# MEC8_Expansion.net
KiCad netlist of a schematic drawn in Altium Designer
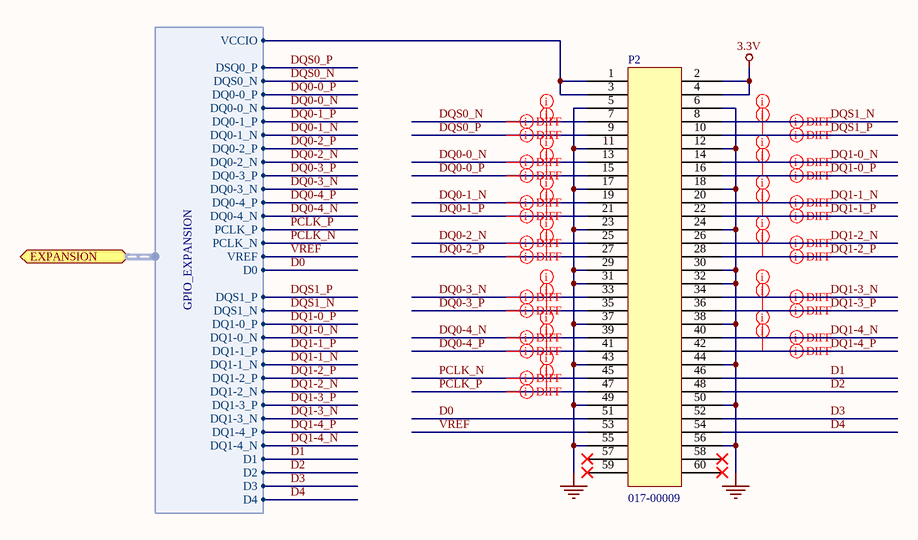
[diagram p0: MEC8_Expansion.SchDoc]

(export (version "E")
  (design (tool "Eeschema 10.0.6"))
  (components
    (comp (ref "P2")
      (value "~")
      (footprint "005-00021")
      (description "CONN RCPT MEC8 60 POS")
      (fields
        (field (name "PART NUMBER") "017-00009")
        (field (name "MANUFACTURER1 PART NUMBER") "MEC8-130-02-L-D-RA1")
      )
      (libsource (lib "CES Component Library") (part "004-00019"))
    )
  )
  (nets
    (net (code "2") (name "/D0") (class "Default")
      (node (ref "P2") (pin "51") (pinfunction "51_51") (pintype "passive"))
    )
    (net (code "3") (name "/D1") (class "Default")
      (node (ref "P2") (pin "46") (pinfunction "46_46") (pintype "passive"))
    )
    (net (code "4") (name "/D2") (class "Default")
      (node (ref "P2") (pin "48") (pinfunction "48_48") (pintype "passive"))
    )
    (net (code "5") (name "/D3") (class "Default")
      (node (ref "P2") (pin "52") (pinfunction "52_52") (pintype "passive"))
    )
    (net (code "6") (name "/D4") (class "Default")
      (node (ref "P2") (pin "54") (pinfunction "54_54") (pintype "passive"))
    )
    (net (code "7") (name "/DQ0-0_N") (class "Default")
      (node (ref "P2") (pin "13") (pinfunction "13_13") (pintype "passive"))
    )
    (net (code "8") (name "/DQ0-0_P") (class "Default")
      (node (ref "P2") (pin "15") (pinfunction "15_15") (pintype "passive"))
    )
    (net (code "9") (name "/DQ0-1_N") (class "Default")
      (node (ref "P2") (pin "19") (pinfunction "19_19") (pintype "passive"))
    )
    (net (code "10") (name "/DQ0-1_P") (class "Default")
      (node (ref "P2") (pin "21") (pinfunction "21_21") (pintype "passive"))
    )
    (net (code "11") (name "/DQ0-2_N") (class "Default")
      (node (ref "P2") (pin "25") (pinfunction "25_25") (pintype "passive"))
    )
    (net (code "12") (name "/DQ0-2_P") (class "Default")
      (node (ref "P2") (pin "27") (pinfunction "27_27") (pintype "passive"))
    )
    (net (code "13") (name "/DQ0-3_N") (class "Default")
      (node (ref "P2") (pin "33") (pinfunction "33_33") (pintype "passive"))
    )
    (net (code "14") (name "/DQ0-3_P") (class "Default")
      (node (ref "P2") (pin "35") (pinfunction "35_35") (pintype "passive"))
    )
    (net (code "15") (name "/DQ0-4_N") (class "Default")
      (node (ref "P2") (pin "39") (pinfunction "39_39") (pintype "passive"))
    )
    (net (code "16") (name "/DQ0-4_P") (class "Default")
      (node (ref "P2") (pin "41") (pinfunction "41_41") (pintype "passive"))
    )
    (net (code "17") (name "/DQ1-0_N") (class "Default")
      (node (ref "P2") (pin "14") (pinfunction "14_14") (pintype "passive"))
    )
    (net (code "18") (name "/DQ1-0_P") (class "Default")
      (node (ref "P2") (pin "16") (pinfunction "16_16") (pintype "passive"))
    )
    (net (code "19") (name "/DQ1-1_N") (class "Default")
      (node (ref "P2") (pin "20") (pinfunction "20_20") (pintype "passive"))
    )
    (net (code "20") (name "/DQ1-1_P") (class "Default")
      (node (ref "P2") (pin "22") (pinfunction "22_22") (pintype "passive"))
    )
    (net (code "21") (name "/DQ1-2_N") (class "Default")
      (node (ref "P2") (pin "26") (pinfunction "26_26") (pintype "passive"))
    )
    (net (code "22") (name "/DQ1-2_P") (class "Default")
      (node (ref "P2") (pin "28") (pinfunction "28_28") (pintype "passive"))
    )
    (net (code "23") (name "/DQ1-3_N") (class "Default")
      (node (ref "P2") (pin "34") (pinfunction "34_34") (pintype "passive"))
    )
    (net (code "24") (name "/DQ1-3_P") (class "Default")
      (node (ref "P2") (pin "36") (pinfunction "36_36") (pintype "passive"))
    )
    (net (code "25") (name "/DQ1-4_N") (class "Default")
      (node (ref "P2") (pin "40") (pinfunction "40_40") (pintype "passive"))
    )
    (net (code "26") (name "/DQ1-4_P") (class "Default")
      (node (ref "P2") (pin "42") (pinfunction "42_42") (pintype "passive"))
    )
    (net (code "27") (name "/DQS0_N") (class "Default")
      (node (ref "P2") (pin "7") (pinfunction "7_7") (pintype "passive"))
    )
    (net (code "28") (name "/DQS0_P") (class "Default")
      (node (ref "P2") (pin "9") (pinfunction "9_9") (pintype "passive"))
    )
    (net (code "29") (name "/DQS1_N") (class "Default")
      (node (ref "P2") (pin "8") (pinfunction "8_8") (pintype "passive"))
    )
    (net (code "30") (name "/DQS1_P") (class "Default")
      (node (ref "P2") (pin "10") (pinfunction "10_10") (pintype "passive"))
    )
    (net (code "31") (name "/PCLK_N") (class "Default")
      (node (ref "P2") (pin "45") (pinfunction "45_45") (pintype "passive"))
    )
    (net (code "32") (name "/PCLK_P") (class "Default")
      (node (ref "P2") (pin "47") (pinfunction "47_47") (pintype "passive"))
    )
    (net (code "33") (name "/VREF") (class "Default")
      (node (ref "P2") (pin "53") (pinfunction "53_53") (pintype "passive"))
    )
    (net (code "35") (name "3.3V") (class "Default")
      (node (ref "P2") (pin "2") (pinfunction "2_2") (pintype "passive"))
      (node (ref "P2") (pin "4") (pinfunction "4_4") (pintype "passive"))
    )
    (net (code "36") (name "GND") (class "Default")
      (node (ref "P2") (pin "11") (pinfunction "11_11") (pintype "passive"))
      (node (ref "P2") (pin "12") (pinfunction "12_12") (pintype "passive"))
      (node (ref "P2") (pin "17") (pinfunction "17_17") (pintype "passive"))
      (node (ref "P2") (pin "18") (pinfunction "18_18") (pintype "passive"))
      (node (ref "P2") (pin "23") (pinfunction "23_23") (pintype "passive"))
      (node (ref "P2") (pin "24") (pinfunction "24_24") (pintype "passive"))
      (node (ref "P2") (pin "29") (pinfunction "29_29") (pintype "passive"))
      (node (ref "P2") (pin "30") (pinfunction "30_30") (pintype "passive"))
      (node (ref "P2") (pin "31") (pinfunction "31_31") (pintype "passive"))
      (node (ref "P2") (pin "32") (pinfunction "32_32") (pintype "passive"))
      (node (ref "P2") (pin "37") (pinfunction "37_37") (pintype "passive"))
      (node (ref "P2") (pin "38") (pinfunction "38_38") (pintype "passive"))
      (node (ref "P2") (pin "43") (pinfunction "43_43") (pintype "passive"))
      (node (ref "P2") (pin "44") (pinfunction "44_44") (pintype "passive"))
      (node (ref "P2") (pin "49") (pinfunction "49_49") (pintype "passive"))
      (node (ref "P2") (pin "5") (pinfunction "5_5") (pintype "passive"))
      (node (ref "P2") (pin "50") (pinfunction "50_50") (pintype "passive"))
      (node (ref "P2") (pin "55") (pinfunction "55_55") (pintype "passive"))
      (node (ref "P2") (pin "56") (pinfunction "56_56") (pintype "passive"))
      (node (ref "P2") (pin "6") (pinfunction "6_6") (pintype "passive"))
    )
    (net (code "37") (name "Net-(P2-Pad1)") (class "Default")
      (node (ref "P2") (pin "1") (pinfunction "1_1") (pintype "passive"))
      (node (ref "P2") (pin "3") (pinfunction "3_3") (pintype "passive"))
    )
    (net (code "38") (name "unconnected-(P2-Pad57)") (class "Default")
      (node (ref "P2") (pin "57") (pinfunction "57_57") (pintype "passive+no_connect"))
    )
    (net (code "39") (name "unconnected-(P2-Pad58)") (class "Default")
      (node (ref "P2") (pin "58") (pinfunction "58_58") (pintype "passive+no_connect"))
    )
    (net (code "40") (name "unconnected-(P2-Pad59)") (class "Default")
      (node (ref "P2") (pin "59") (pinfunction "59_59") (pintype "passive+no_connect"))
    )
    (net (code "41") (name "unconnected-(P2-Pad60)") (class "Default")
      (node (ref "P2") (pin "60") (pinfunction "60_60") (pintype "passive+no_connect"))
    )
  )
)
